# ee242a-lab6-amp-osc.net
KiCad netlist of a schematic drawn in EAGLE
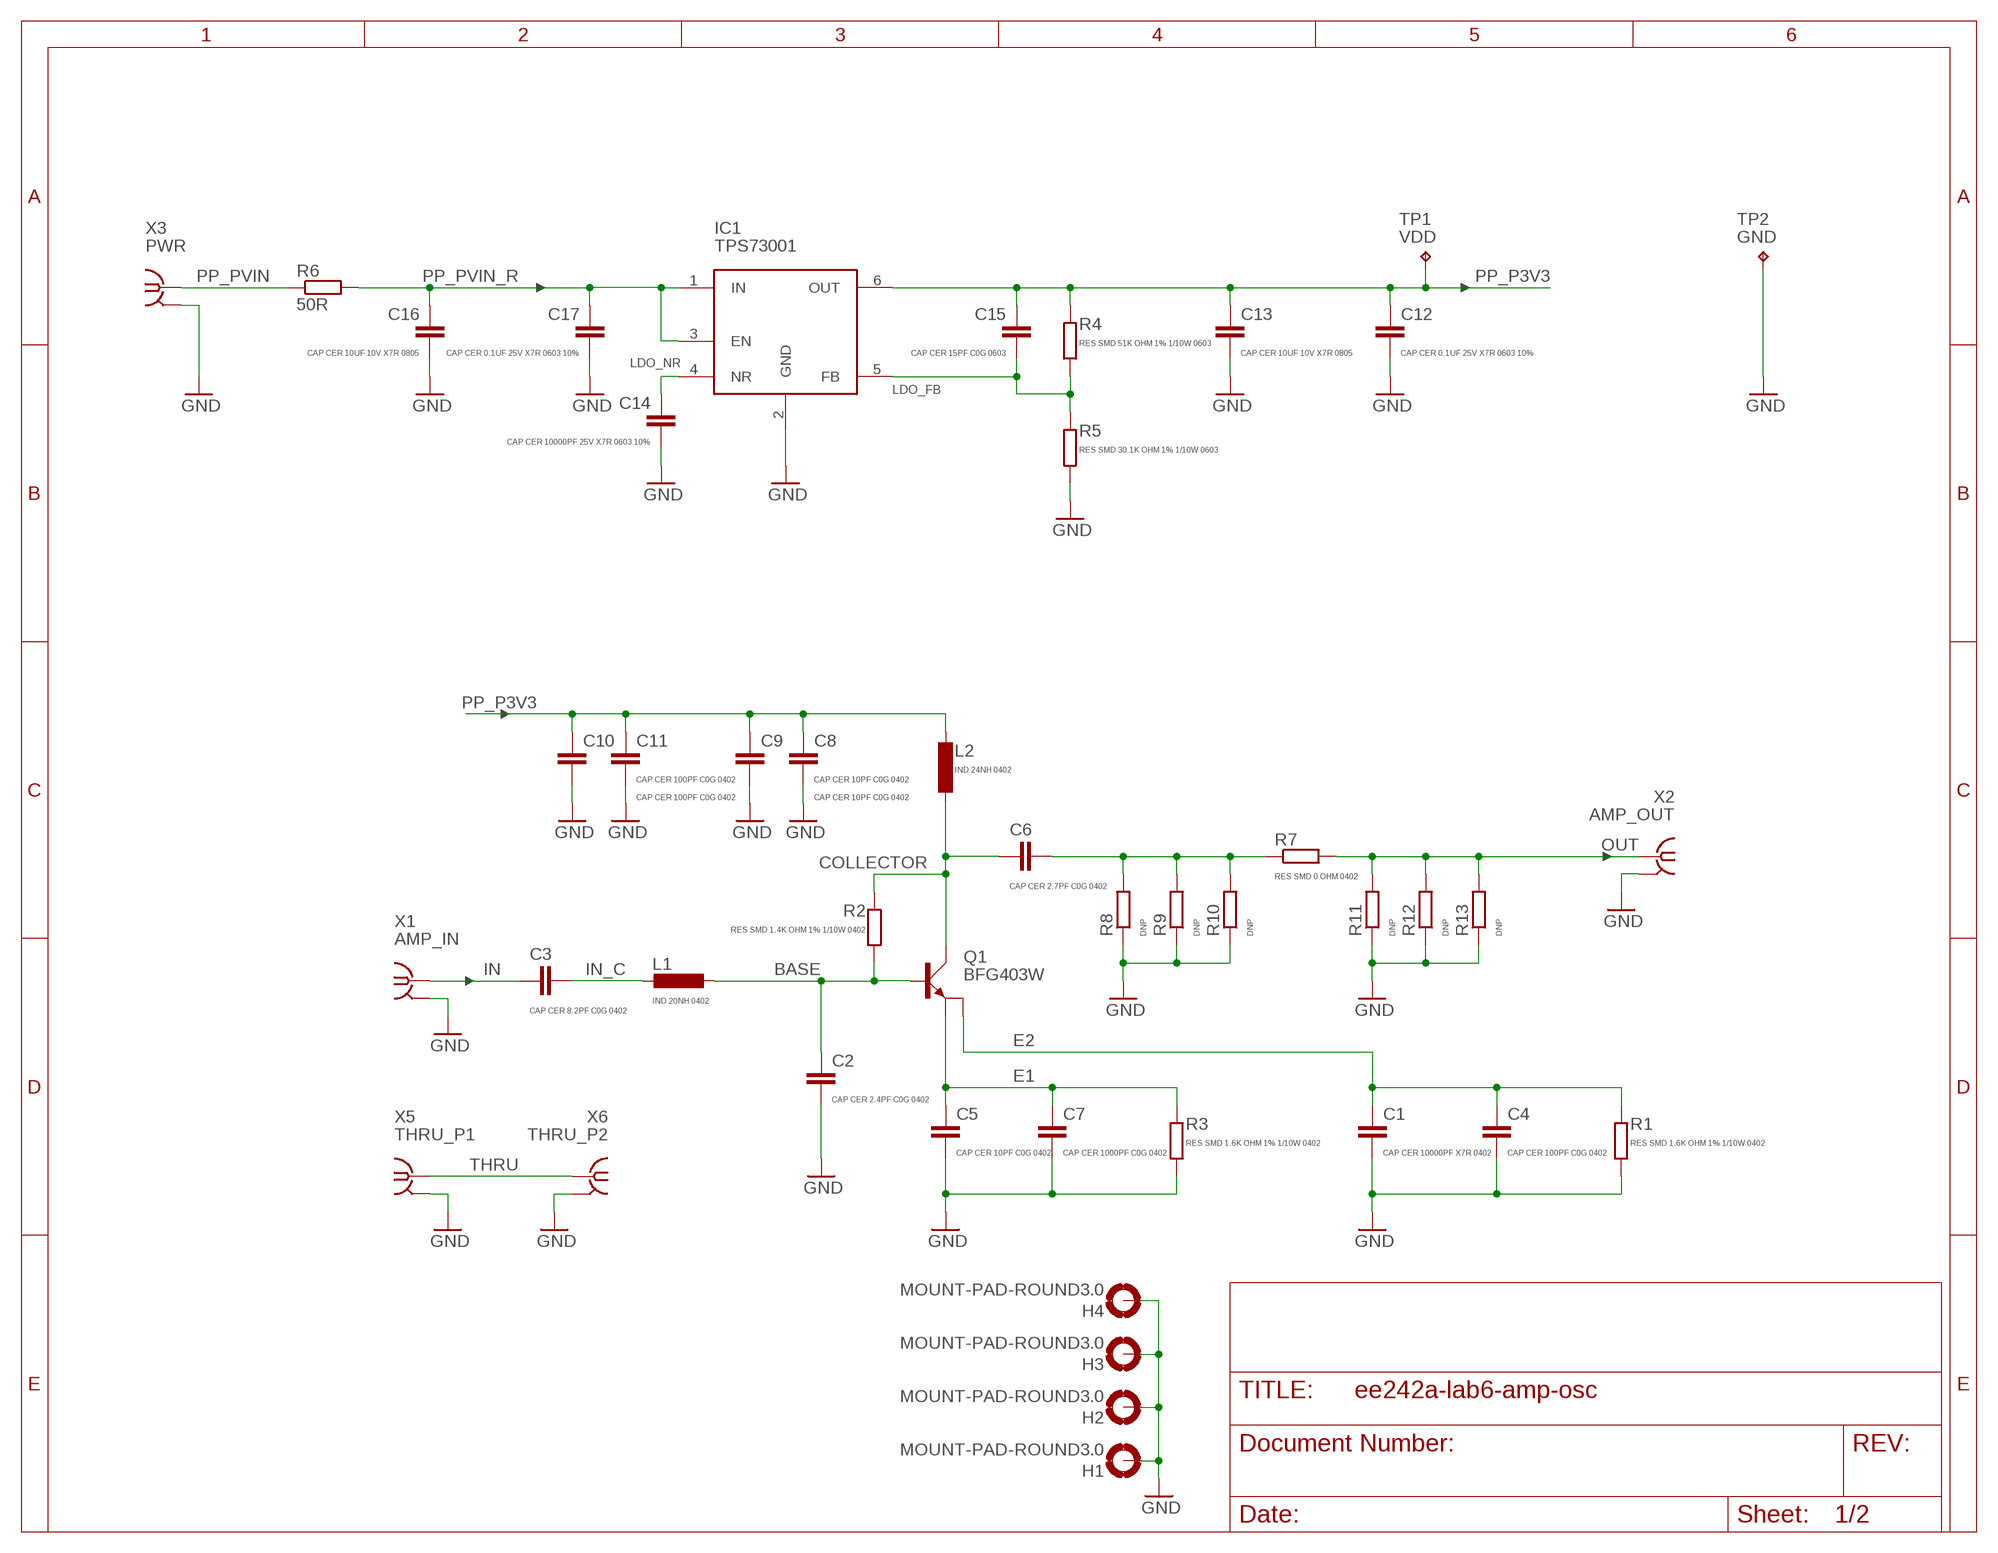
[diagram p0: schematic, sheet 1]
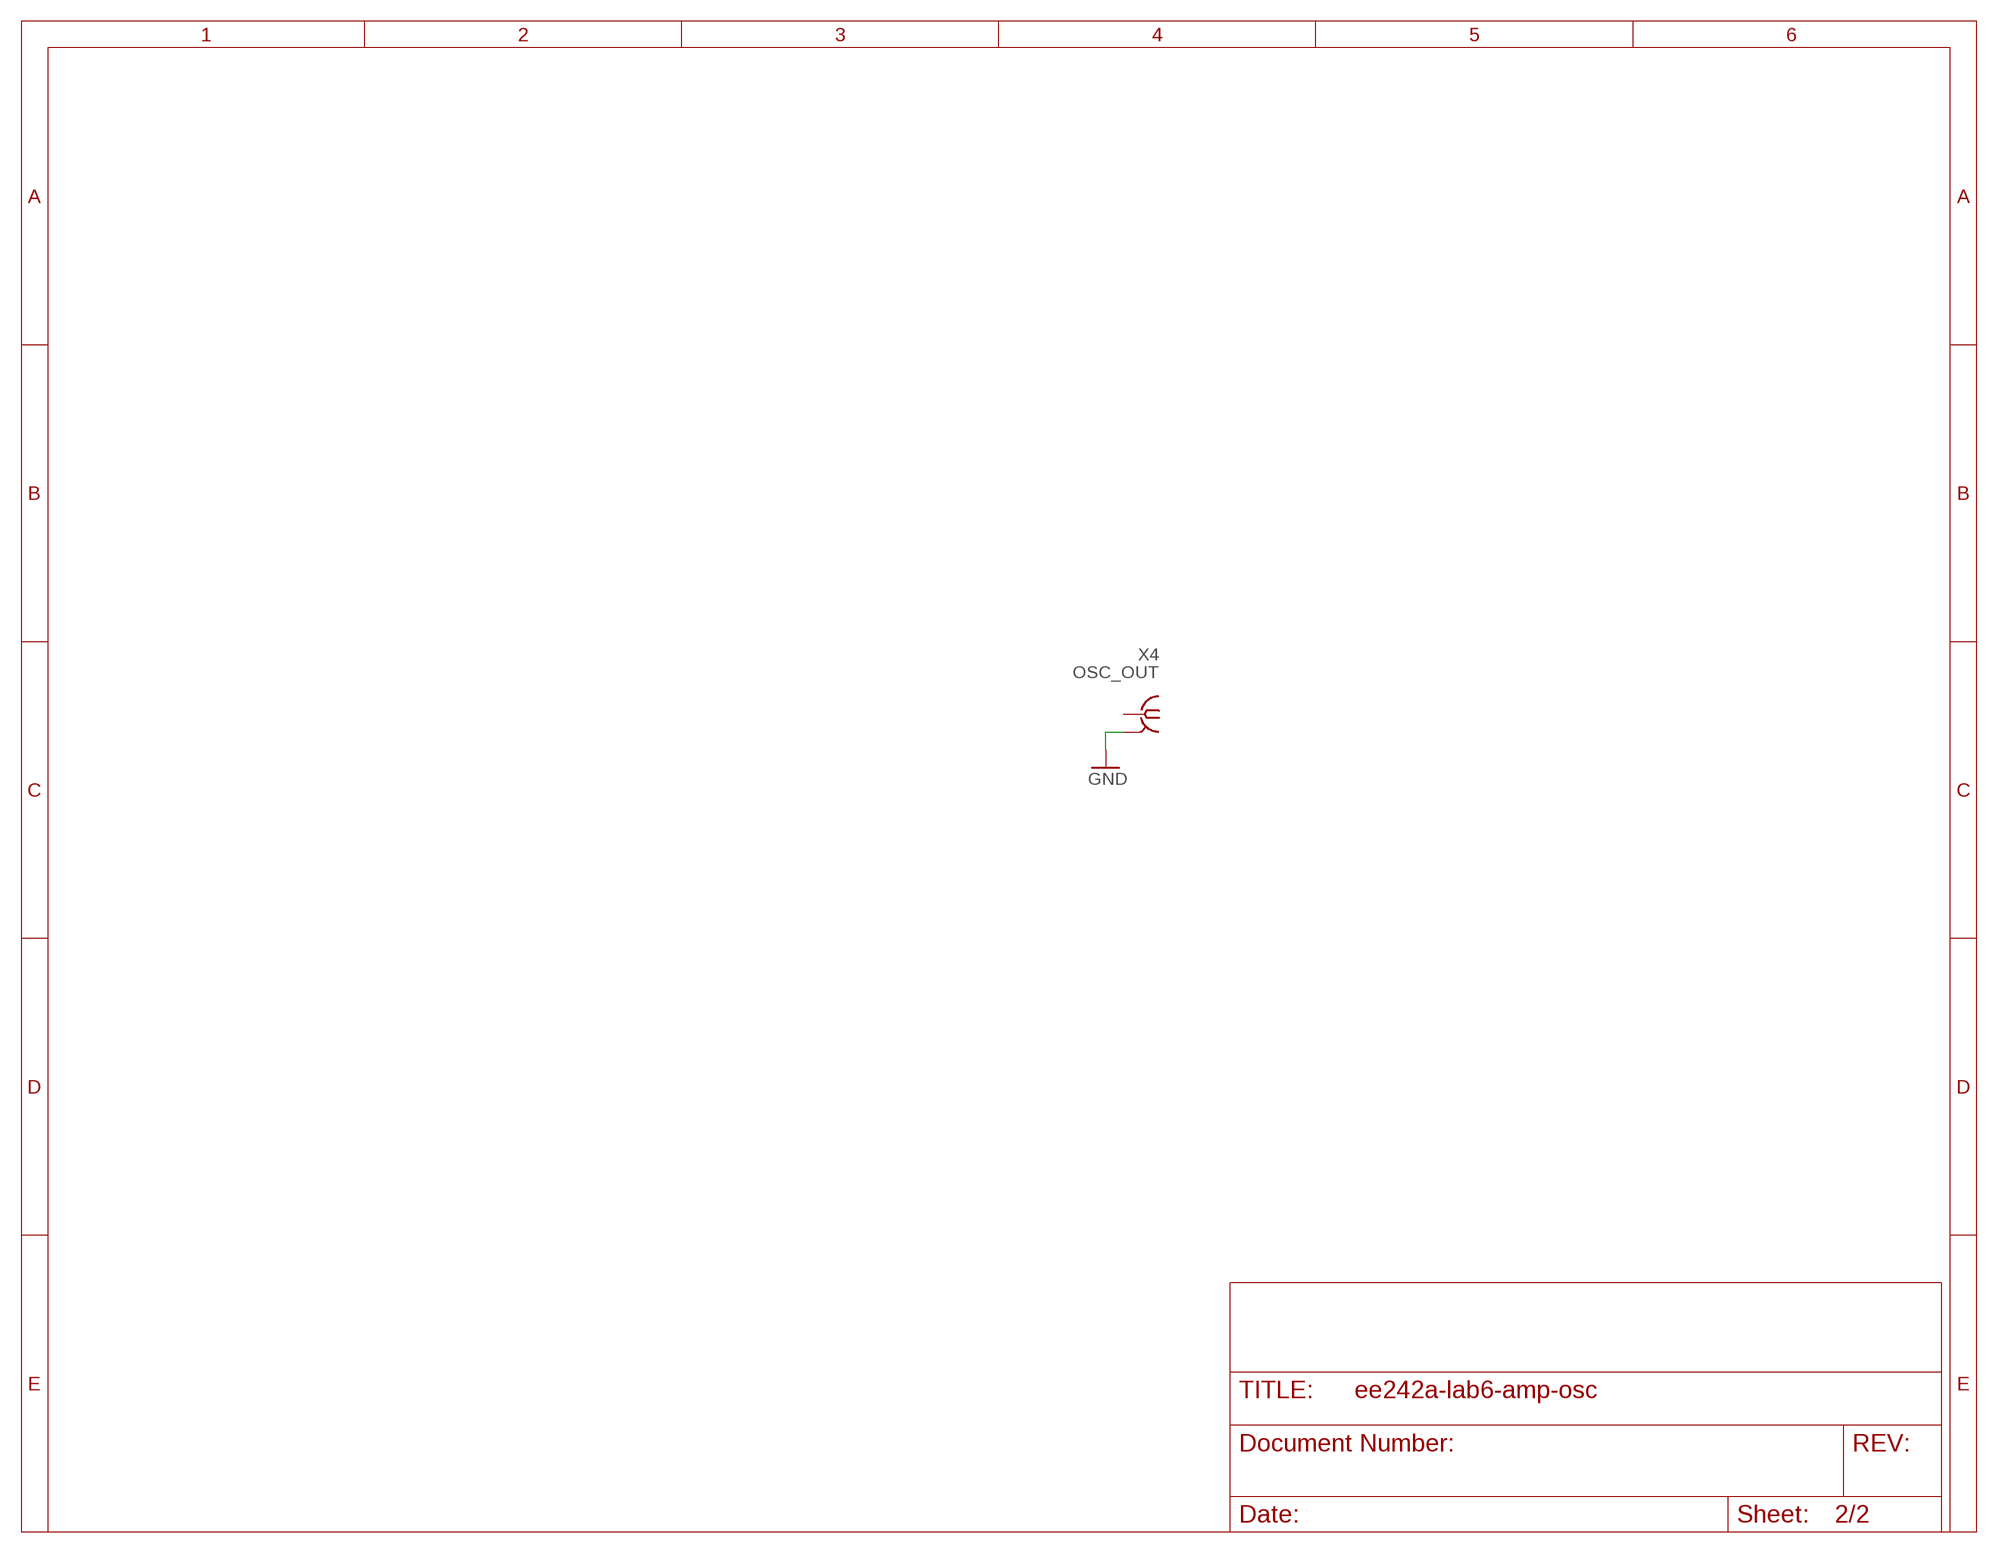
[diagram p1: schematic, sheet 2]

(export (version "E")
  (design (tool "Eeschema 10.0.6"))
  (components
    (comp (ref "C1")
      (value "CAP CER 10000PF X7R 0402")
      (footprint "eagle-import:C0402")
      (libsource (lib "eagle-import") (part "rcl-modified-footprints_C-EUC0402"))
    )
    (comp (ref "C2")
      (value "CAP CER 2.4PF C0G 0402")
      (footprint "eagle-import:C0402")
      (libsource (lib "eagle-import") (part "rcl-modified-footprints_C-EUC0402"))
    )
    (comp (ref "C3")
      (value "CAP CER 8.2PF C0G 0402")
      (footprint "eagle-import:C0402")
      (libsource (lib "eagle-import") (part "rcl-modified-footprints_C-EUC0402"))
    )
    (comp (ref "C4")
      (value "CAP CER 100PF C0G 0402")
      (footprint "eagle-import:C0402")
      (libsource (lib "eagle-import") (part "rcl-modified-footprints_C-EUC0402"))
    )
    (comp (ref "C5")
      (value "CAP CER 10PF C0G 0402")
      (footprint "eagle-import:C0402")
      (libsource (lib "eagle-import") (part "rcl-modified-footprints_C-EUC0402"))
    )
    (comp (ref "C6")
      (value "CAP CER 2.7PF C0G 0402")
      (footprint "eagle-import:C0402")
      (libsource (lib "eagle-import") (part "rcl-modified-footprints_C-EUC0402"))
    )
    (comp (ref "C7")
      (value "CAP CER 1000PF C0G 0402")
      (footprint "eagle-import:C0402")
      (libsource (lib "eagle-import") (part "rcl-modified-footprints_C-EUC0402"))
    )
    (comp (ref "C8")
      (value "CAP CER 10PF C0G 0402")
      (footprint "eagle-import:C0402")
      (libsource (lib "eagle-import") (part "rcl-modified-footprints_C-EUC0402"))
    )
    (comp (ref "C9")
      (value "CAP CER 10PF C0G 0402")
      (footprint "eagle-import:C0402")
      (libsource (lib "eagle-import") (part "rcl-modified-footprints_C-EUC0402"))
    )
    (comp (ref "C10")
      (value "CAP CER 100PF C0G 0402")
      (footprint "eagle-import:C0402")
      (libsource (lib "eagle-import") (part "rcl-modified-footprints_C-EUC0402"))
    )
    (comp (ref "C11")
      (value "CAP CER 100PF C0G 0402")
      (footprint "eagle-import:C0402")
      (libsource (lib "eagle-import") (part "rcl-modified-footprints_C-EUC0402"))
    )
    (comp (ref "C12")
      (value "CAP CER 0.1UF 25V X7R 0603 10%")
      (footprint "eagle-import:C0603")
      (libsource (lib "eagle-import") (part "rcl-modified-footprints_C-EUC0603"))
    )
    (comp (ref "C13")
      (value "CAP CER 10UF 10V X7R 0805")
      (footprint "eagle-import:C0805")
      (libsource (lib "eagle-import") (part "C-EUC0805"))
    )
    (comp (ref "C14")
      (value "CAP CER 10000PF 25V X7R 0603 10%")
      (footprint "eagle-import:C0603")
      (libsource (lib "eagle-import") (part "rcl-modified-footprints_C-EUC0603"))
    )
    (comp (ref "C15")
      (value "CAP CER 15PF C0G 0603")
      (footprint "eagle-import:C0603")
      (libsource (lib "eagle-import") (part "rcl-modified-footprints_C-EUC0603"))
    )
    (comp (ref "C16")
      (value "CAP CER 10UF 10V X7R 0805")
      (footprint "eagle-import:C0805")
      (libsource (lib "eagle-import") (part "C-EUC0805"))
    )
    (comp (ref "C17")
      (value "CAP CER 0.1UF 25V X7R 0603 10%")
      (footprint "eagle-import:C0603")
      (libsource (lib "eagle-import") (part "rcl-modified-footprints_C-EUC0603"))
    )
    (comp (ref "H1")
      (value "MOUNT-PAD-ROUND3.0")
      (footprint "eagle-import:3,0-PAD")
      (libsource (lib "eagle-import") (part "MOUNT-PAD-ROUND3.0"))
    )
    (comp (ref "H2")
      (value "MOUNT-PAD-ROUND3.0")
      (footprint "eagle-import:3,0-PAD")
      (libsource (lib "eagle-import") (part "MOUNT-PAD-ROUND3.0"))
    )
    (comp (ref "H3")
      (value "MOUNT-PAD-ROUND3.0")
      (footprint "eagle-import:3,0-PAD")
      (libsource (lib "eagle-import") (part "MOUNT-PAD-ROUND3.0"))
    )
    (comp (ref "H4")
      (value "MOUNT-PAD-ROUND3.0")
      (footprint "eagle-import:3,0-PAD")
      (libsource (lib "eagle-import") (part "MOUNT-PAD-ROUND3.0"))
    )
    (comp (ref "IC1")
      (value "TPS73001")
      (footprint "eagle-import:SOT23-6L")
      (libsource (lib "eagle-import") (part "TPS73001"))
    )
    (comp (ref "L1")
      (value "IND 20NH 0402")
      (footprint "eagle-import:R0402")
      (libsource (lib "eagle-import") (part "L-EU0402"))
    )
    (comp (ref "L2")
      (value "IND 24NH 0402")
      (footprint "eagle-import:R0402")
      (libsource (lib "eagle-import") (part "L-EU0402"))
    )
    (comp (ref "Q1")
      (value "BFG403W")
      (footprint "eagle-import:SOT343R")
      (libsource (lib "eagle-import") (part "BFG403W"))
    )
    (comp (ref "R1")
      (value "RES SMD 1.6K OHM 1% 1/10W 0402")
      (footprint "eagle-import:R0402")
      (libsource (lib "eagle-import") (part "R-EU_R0402"))
    )
    (comp (ref "R2")
      (value "RES SMD 1.4K OHM 1% 1/10W 0402")
      (footprint "eagle-import:R0402")
      (libsource (lib "eagle-import") (part "R-EU_R0402"))
    )
    (comp (ref "R3")
      (value "RES SMD 1.6K OHM 1% 1/10W 0402")
      (footprint "eagle-import:R0402")
      (libsource (lib "eagle-import") (part "R-EU_R0402"))
    )
    (comp (ref "R4")
      (value "RES SMD 51K OHM 1% 1/10W 0603")
      (footprint "eagle-import:R0603")
      (libsource (lib "eagle-import") (part "R-EU_R0603"))
    )
    (comp (ref "R5")
      (value "RES SMD 30.1K OHM 1% 1/10W 0603")
      (footprint "eagle-import:R0603")
      (libsource (lib "eagle-import") (part "R-EU_R0603"))
    )
    (comp (ref "R6")
      (value "50R")
      (footprint "eagle-import:R0805")
      (libsource (lib "eagle-import") (part "R-EU_R0805"))
    )
    (comp (ref "R7")
      (value "RES SMD 0 OHM 0402")
      (footprint "eagle-import:R0402")
      (libsource (lib "eagle-import") (part "R-EU_R0402"))
    )
    (comp (ref "R8")
      (value "DNP")
      (footprint "eagle-import:R0402")
      (libsource (lib "eagle-import") (part "R-EU_R0402"))
    )
    (comp (ref "R9")
      (value "DNP")
      (footprint "eagle-import:R0402")
      (libsource (lib "eagle-import") (part "R-EU_R0402"))
    )
    (comp (ref "R10")
      (value "DNP")
      (footprint "eagle-import:R0402")
      (libsource (lib "eagle-import") (part "R-EU_R0402"))
    )
    (comp (ref "R11")
      (value "DNP")
      (footprint "eagle-import:R0402")
      (libsource (lib "eagle-import") (part "R-EU_R0402"))
    )
    (comp (ref "R12")
      (value "DNP")
      (footprint "eagle-import:R0402")
      (libsource (lib "eagle-import") (part "R-EU_R0402"))
    )
    (comp (ref "R13")
      (value "DNP")
      (footprint "eagle-import:R0402")
      (libsource (lib "eagle-import") (part "R-EU_R0402"))
    )
    (comp (ref "TP1")
      (value "VDD")
      (footprint "eagle-import:KEYSTONE_5000_MINIATURE")
      (libsource (lib "eagle-import") (part "KEYSTONE_5000"))
    )
    (comp (ref "TP2")
      (value "GND")
      (footprint "eagle-import:KEYSTONE_5000_MINIATURE")
      (libsource (lib "eagle-import") (part "KEYSTONE_5000"))
    )
    (comp (ref "X1")
      (value "AMP_IN")
      (footprint "eagle-import:J502-ND-142-0701-881_886")
      (fields (field (name "MF") "JOHNSON COMPONENTS") (field (name "MPN") "142-0701-881"))
      (libsource (lib "eagle-import") (part "SMA-142-0701-881/886"))
    )
    (comp (ref "X2")
      (value "AMP_OUT")
      (footprint "eagle-import:J502-ND-142-0701-881_886")
      (fields (field (name "MF") "JOHNSON COMPONENTS") (field (name "MPN") "142-0701-881"))
      (libsource (lib "eagle-import") (part "SMA-142-0701-881/886"))
    )
    (comp (ref "X3")
      (value "PWR")
      (footprint "eagle-import:J502-ND-142-0701-881_886")
      (fields (field (name "MF") "JOHNSON COMPONENTS") (field (name "MPN") "142-0701-881"))
      (libsource (lib "eagle-import") (part "SMA-142-0701-881/886"))
    )
    (comp (ref "X5")
      (value "THRU_P1")
      (footprint "eagle-import:J502-ND-142-0701-881_886")
      (fields (field (name "MF") "JOHNSON COMPONENTS") (field (name "MPN") "142-0701-881"))
      (libsource (lib "eagle-import") (part "SMA-142-0701-881/886"))
    )
    (comp (ref "X6")
      (value "THRU_P2")
      (footprint "eagle-import:J502-ND-142-0701-881_886")
      (fields (field (name "MF") "JOHNSON COMPONENTS") (field (name "MPN") "142-0701-881"))
      (libsource (lib "eagle-import") (part "SMA-142-0701-881/886"))
    )
    (comp (ref "X4")
      (value "OSC_OUT")
      (footprint "eagle-import:J502-ND-142-0701-881_886")
      (fields (field (name "MF") "JOHNSON COMPONENTS") (field (name "MPN") "142-0701-881"))
      (libsource (lib "eagle-import") (part "SMA-142-0701-881/886"))
    )
  )
  (nets
    (net (code "1") (name "BASE") (class "Default")
      (node (ref "C2") (pin "1") (pinfunction "1_1") (pintype "passive"))
      (node (ref "L1") (pin "2") (pinfunction "2_2") (pintype "passive"))
      (node (ref "Q1") (pin "2") (pinfunction "B_2") (pintype "passive"))
      (node (ref "R2") (pin "2") (pinfunction "2_2") (pintype "passive"))
    )
    (net (code "2") (name "COLLECTOR") (class "Default")
      (node (ref "C6") (pin "1") (pinfunction "1_1") (pintype "passive"))
      (node (ref "L2") (pin "2") (pinfunction "2_2") (pintype "passive"))
      (node (ref "Q1") (pin "4") (pinfunction "C_4") (pintype "passive"))
      (node (ref "R2") (pin "1") (pinfunction "1_1") (pintype "passive"))
    )
    (net (code "3") (name "E1") (class "Default")
      (node (ref "C5") (pin "1") (pinfunction "1_1") (pintype "passive"))
      (node (ref "C7") (pin "1") (pinfunction "1_1") (pintype "passive"))
      (node (ref "Q1") (pin "1") (pinfunction "E1_1") (pintype "passive"))
      (node (ref "R3") (pin "1") (pinfunction "1_1") (pintype "passive"))
    )
    (net (code "4") (name "E2") (class "Default")
      (node (ref "C1") (pin "1") (pinfunction "1_1") (pintype "passive"))
      (node (ref "C4") (pin "1") (pinfunction "1_1") (pintype "passive"))
      (node (ref "Q1") (pin "3") (pinfunction "E2_3") (pintype "passive"))
      (node (ref "R1") (pin "1") (pinfunction "1_1") (pintype "passive"))
    )
    (net (code "5") (name "GND") (class "Default")
      (node (ref "C1") (pin "2") (pinfunction "2_2") (pintype "passive"))
      (node (ref "C10") (pin "2") (pinfunction "2_2") (pintype "passive"))
      (node (ref "C11") (pin "2") (pinfunction "2_2") (pintype "passive"))
      (node (ref "C12") (pin "2") (pinfunction "2_2") (pintype "passive"))
      (node (ref "C13") (pin "2") (pinfunction "2_2") (pintype "passive"))
      (node (ref "C14") (pin "2") (pinfunction "2_2") (pintype "passive"))
      (node (ref "C16") (pin "2") (pinfunction "2_2") (pintype "passive"))
      (node (ref "C17") (pin "2") (pinfunction "2_2") (pintype "passive"))
      (node (ref "C2") (pin "2") (pinfunction "2_2") (pintype "passive"))
      (node (ref "C4") (pin "2") (pinfunction "2_2") (pintype "passive"))
      (node (ref "C5") (pin "2") (pinfunction "2_2") (pintype "passive"))
      (node (ref "C7") (pin "2") (pinfunction "2_2") (pintype "passive"))
      (node (ref "C8") (pin "2") (pinfunction "2_2") (pintype "passive"))
      (node (ref "C9") (pin "2") (pinfunction "2_2") (pintype "passive"))
      (node (ref "H1") (pin "B3,0") (pinfunction "MOUNT_B3,0") (pintype "passive"))
      (node (ref "H2") (pin "B3,0") (pinfunction "MOUNT_B3,0") (pintype "passive"))
      (node (ref "H3") (pin "B3,0") (pinfunction "MOUNT_B3,0") (pintype "passive"))
      (node (ref "H4") (pin "B3,0") (pinfunction "MOUNT_B3,0") (pintype "passive"))
      (node (ref "IC1") (pin "2") (pinfunction "GND_2") (pintype "bidirectional"))
      (node (ref "R1") (pin "2") (pinfunction "2_2") (pintype "passive"))
      (node (ref "R10") (pin "1") (pinfunction "1_1") (pintype "passive"))
      (node (ref "R11") (pin "1") (pinfunction "1_1") (pintype "passive"))
      (node (ref "R12") (pin "1") (pinfunction "1_1") (pintype "passive"))
      (node (ref "R13") (pin "1") (pinfunction "1_1") (pintype "passive"))
      (node (ref "R3") (pin "2") (pinfunction "2_2") (pintype "passive"))
      (node (ref "R5") (pin "2") (pinfunction "2_2") (pintype "passive"))
      (node (ref "R8") (pin "1") (pinfunction "1_1") (pintype "passive"))
      (node (ref "R9") (pin "1") (pinfunction "1_1") (pintype "passive"))
      (node (ref "TP2") (pin "P$1") (pinfunction "P$1_P$1") (pintype "bidirectional"))
      (node (ref "X1") (pin "G@1") (pinfunction "GND_G@1") (pintype "power_in"))
      (node (ref "X2") (pin "G@1") (pinfunction "GND_G@1") (pintype "power_in"))
      (node (ref "X3") (pin "G@1") (pinfunction "GND_G@1") (pintype "power_in"))
      (node (ref "X4") (pin "G@1") (pinfunction "GND_G@1") (pintype "power_in"))
      (node (ref "X5") (pin "G@1") (pinfunction "GND_G@1") (pintype "power_in"))
      (node (ref "X6") (pin "G@1") (pinfunction "GND_G@1") (pintype "power_in"))
    )
    (net (code "6") (name "IN") (class "Default")
      (node (ref "C3") (pin "1") (pinfunction "1_1") (pintype "passive"))
      (node (ref "X1") (pin "1") (pinfunction "1_1") (pintype "passive"))
    )
    (net (code "7") (name "IN_C") (class "Default")
      (node (ref "C3") (pin "2") (pinfunction "2_2") (pintype "passive"))
      (node (ref "L1") (pin "1") (pinfunction "1_1") (pintype "passive"))
    )
    (net (code "8") (name "LDO_FB") (class "Default")
      (node (ref "C15") (pin "2") (pinfunction "2_2") (pintype "passive"))
      (node (ref "IC1") (pin "5") (pinfunction "FB_5") (pintype "bidirectional"))
      (node (ref "R4") (pin "1") (pinfunction "1_1") (pintype "passive"))
      (node (ref "R5") (pin "1") (pinfunction "1_1") (pintype "passive"))
    )
    (net (code "9") (name "LDO_NR") (class "Default")
      (node (ref "C14") (pin "1") (pinfunction "1_1") (pintype "passive"))
      (node (ref "IC1") (pin "4") (pinfunction "NR_4") (pintype "bidirectional"))
    )
    (net (code "10") (name "Net-(C6-Pad2)") (class "Default")
      (node (ref "C6") (pin "2") (pinfunction "2_2") (pintype "passive"))
      (node (ref "R10") (pin "2") (pinfunction "2_2") (pintype "passive"))
      (node (ref "R7") (pin "1") (pinfunction "1_1") (pintype "passive"))
      (node (ref "R8") (pin "2") (pinfunction "2_2") (pintype "passive"))
      (node (ref "R9") (pin "2") (pinfunction "2_2") (pintype "passive"))
    )
    (net (code "11") (name "OUT") (class "Default")
      (node (ref "R11") (pin "2") (pinfunction "2_2") (pintype "passive"))
      (node (ref "R12") (pin "2") (pinfunction "2_2") (pintype "passive"))
      (node (ref "R13") (pin "2") (pinfunction "2_2") (pintype "passive"))
      (node (ref "R7") (pin "2") (pinfunction "2_2") (pintype "passive"))
      (node (ref "X2") (pin "1") (pinfunction "1_1") (pintype "passive"))
    )
    (net (code "12") (name "PP_P3V3") (class "Default")
      (node (ref "C10") (pin "1") (pinfunction "1_1") (pintype "passive"))
      (node (ref "C11") (pin "1") (pinfunction "1_1") (pintype "passive"))
      (node (ref "C12") (pin "1") (pinfunction "1_1") (pintype "passive"))
      (node (ref "C13") (pin "1") (pinfunction "1_1") (pintype "passive"))
      (node (ref "C15") (pin "1") (pinfunction "1_1") (pintype "passive"))
      (node (ref "C8") (pin "1") (pinfunction "1_1") (pintype "passive"))
      (node (ref "C9") (pin "1") (pinfunction "1_1") (pintype "passive"))
      (node (ref "IC1") (pin "6") (pinfunction "OUT_6") (pintype "bidirectional"))
      (node (ref "L2") (pin "1") (pinfunction "1_1") (pintype "passive"))
      (node (ref "R4") (pin "2") (pinfunction "2_2") (pintype "passive"))
      (node (ref "TP1") (pin "P$1") (pinfunction "P$1_P$1") (pintype "bidirectional"))
    )
    (net (code "13") (name "PP_PVIN") (class "Default")
      (node (ref "R6") (pin "1") (pinfunction "1_1") (pintype "passive"))
      (node (ref "X3") (pin "1") (pinfunction "1_1") (pintype "passive"))
    )
    (net (code "14") (name "PP_PVIN_R") (class "Default")
      (node (ref "C16") (pin "1") (pinfunction "1_1") (pintype "passive"))
      (node (ref "C17") (pin "1") (pinfunction "1_1") (pintype "passive"))
      (node (ref "IC1") (pin "1") (pinfunction "IN_1") (pintype "bidirectional"))
      (node (ref "IC1") (pin "3") (pinfunction "EN_3") (pintype "bidirectional"))
      (node (ref "R6") (pin "2") (pinfunction "2_2") (pintype "passive"))
    )
    (net (code "15") (name "THRU") (class "Default")
      (node (ref "X5") (pin "1") (pinfunction "1_1") (pintype "passive"))
      (node (ref "X6") (pin "1") (pinfunction "1_1") (pintype "passive"))
    )
    (net (code "16") (name "unconnected-(X4-Pad1)") (class "Default")
      (node (ref "X4") (pin "1") (pinfunction "1_1") (pintype "passive"))
    )
  )
)
